# 24V_5V_Buck.net
KiCad netlist of a schematic drawn in Altium Designer
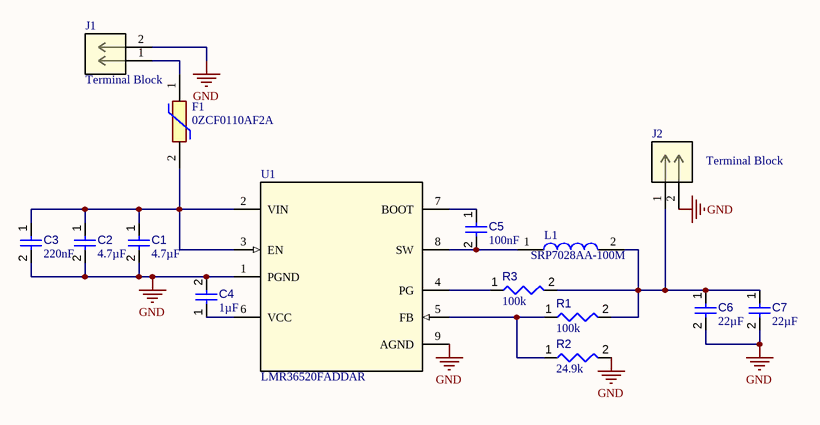
[diagram p0: 24V_5V_Buck.SchDoc]

(export (version "E")
  (design (tool "Eeschema 10.0.6"))
  (components
    (comp (ref "C1")
      (value "4.7µF")
      (footprint "CAPC0603(1608)100_L")
      (description "Chip Capacitor, 4.7µF +/-20%, 10V, 0603, Thickness 1 mm")
      (fields (field (name "TOLERANCE") "10%") (field (name "Comment") "Capacitor 4.7µF +/-20% 10V 0603"))
      (libsource (lib "Samuel Daniel Sdn67@UW") (part "CAP-NP-2"))
    )
    (comp (ref "C2")
      (value "4.7µF")
      (footprint "CAPC0603(1608)100_L")
      (description "Chip Capacitor, 4.7µF +/-20%, 10V, 0603, Thickness 1 mm")
      (fields (field (name "TOLERANCE") "10%") (field (name "Comment") "Capacitor 4.7µF +/-20% 10V 0603"))
      (libsource (lib "Samuel Daniel Sdn67@UW") (part "CAP-NP-2"))
    )
    (comp (ref "C3")
      (value "220nF")
      (footprint "CAPC0402(1005)60_L")
      (description "Chip Capacitor, 220nF +/-20%, 10V, 0402, Thickness 0.6 mm")
      (fields (field (name "TOLERANCE") "10%") (field (name "Comment") "Capacitor 220nF +/-20% 10V 0402"))
      (libsource (lib "Samuel Daniel Sdn67@UW") (part "CAP-NP-2"))
    )
    (comp (ref "C4")
      (value "1µF")
      (footprint "CAPC3216X180X20ML20")
      (description "Chip Capacitor, 1 uF, +/- 10%, 25 V, 1206 (3216 Metric)")
      (fields (field (name "TOLERANCE") "10%") (field (name "Comment") "Capacitor 1 uF +/- 10% 25 V 1206"))
      (libsource (lib "Samuel Daniel Sdn67@UW") (part "CAP-NP-2"))
    )
    (comp (ref "C5")
      (value "100nF")
      (footprint "CAPC2013X95X50LL10T25")
      (description "Chip Capacitor, 100 nF, +/- 10%, 50 V, 0805 (2012 Metric)")
      (fields (field (name "TOLERANCE") "10%") (field (name "Comment") "Capacitor 100 nF +/-10% 50 V 0805"))
      (libsource (lib "Samuel Daniel Sdn67@UW") (part "CAP-NP-2"))
    )
    (comp (ref "C6")
      (value "22µF")
      (footprint "CAPC0805(2012)145_L")
      (description "Chip Capacitor, 22µF +/-40%, 16V, 0805, Thickness 1.45 mm")
      (fields (field (name "TOLERANCE") "5%") (field (name "Comment") "Capacitor 22µF +/-40% 16V 0805"))
      (libsource (lib "Samuel Daniel Sdn67@UW") (part "CAP-NP-2"))
    )
    (comp (ref "C7")
      (value "22µF")
      (footprint "CAPC0805(2012)145_L")
      (description "Chip Capacitor, 22µF +/-40%, 16V, 0805, Thickness 1.45 mm")
      (fields (field (name "TOLERANCE") "5%") (field (name "Comment") "Capacitor 22µF +/-40% 16V 0805"))
      (libsource (lib "Samuel Daniel Sdn67@UW") (part "CAP-NP-2"))
    )
    (comp (ref "F1")
      (value "0ZCF0110AF2A")
      (footprint "SamacSys:FUSC7451X170N")
      (description "Resettable Fuse")
      (libsource (lib "SamacSys") (part "0ZCF0110AF2A"))
    )
    (comp (ref "J1")
      (value "Terminal Block")
      (footprint "CONN2_2710002_WRE")
      (description "WR-TBL Terminal block - Wire protector - THT")
      (fields
        (field (name "MANUFACTURER_PART_NUMBER") "691102710002")
        (field (name "COPYRIGHT") "Copyright (C) 2026 Ultra Librarian. All rights reserved.")
      )
      (libsource (lib "691102710002") (part "691102710002"))
    )
    (comp (ref "J2")
      (value "Terminal Block")
      (footprint "CONN2_2710002_WRE")
      (description "WR-TBL Terminal block - Wire protector - THT")
      (fields
        (field (name "MANUFACTURER_PART_NUMBER") "691102710002")
        (field (name "COPYRIGHT") "Copyright (C) 2026 Ultra Librarian. All rights reserved.")
      )
      (libsource (lib "") (part "691102710002_1"))
    )
    (comp (ref "L1")
      (value "SRP7028AA-100M")
      (footprint "INDPM7166X300N")
      (description "Inductor")
      (fields (field (name "MOUSER PART NUMBER") "652-SRP7028AA-100M"))
      (libsource (lib "*") (part "SRP7028AA-100M"))
    )
    (comp (ref "R1")
      (value "100k")
      (footprint "RESC0402(1005)_L")
      (description "Chip Resistor, 100 kOhms, +/-1 %, 63 mW, -55 to 155 degC, 0402")
      (fields (field (name "TOLERANCE") "1%") (field (name "POWER") "63mW"))
      (libsource (lib "Samuel Daniel Sdn67@UW") (part "RES-2"))
    )
    (comp (ref "R2")
      (value "24.9k")
      (footprint "RESC0402(1005)_L")
      (description "Chip Resistor, 24,9 kOhms, +/-1 %, 63 mW, -55 to 155 degC, 0402")
      (fields (field (name "TOLERANCE") "1%") (field (name "POWER") "63mW"))
      (libsource (lib "Samuel Daniel Sdn67@UW") (part "RES-2"))
    )
    (comp (ref "R3")
      (value "100k")
      (footprint "RESC0402(1005)_L")
      (description "Chip Resistor, 100 kOhms, +/-1 %, 63 mW, -55 to 155 degC, 0402")
      (fields (field (name "TOLERANCE") "1%") (field (name "POWER") "63mW"))
      (libsource (lib "Samuel Daniel Sdn67@UW") (part "RES-2"))
    )
    (comp (ref "U1")
      (value "LMR36520FADDAR")
      (footprint "DDA0008J")
      (fields (field (name "COPYRIGHT") "Copyright (C) 2025 Ultra Librarian. All rights reserved."))
      (libsource (lib "LMR36520FADDAR") (part "LMR36520FADDAR"))
    )
  )
  (nets
    (net (code "1") (name "GND") (class "Default")
      (node (ref "C1") (pin "2") (pinfunction "2_2") (pintype "passive"))
      (node (ref "C2") (pin "2") (pinfunction "2_2") (pintype "passive"))
      (node (ref "C3") (pin "2") (pinfunction "2_2") (pintype "passive"))
      (node (ref "C4") (pin "2") (pinfunction "2_2") (pintype "passive"))
      (node (ref "C6") (pin "2") (pinfunction "2_2") (pintype "passive"))
      (node (ref "C7") (pin "2") (pinfunction "2_2") (pintype "passive"))
      (node (ref "J1") (pin "2") (pinfunction "2_2") (pintype "passive"))
      (node (ref "J2") (pin "2") (pinfunction "2_2") (pintype "passive"))
      (node (ref "R2") (pin "2") (pinfunction "2_2") (pintype "passive"))
      (node (ref "U1") (pin "1") (pinfunction "PGND_1") (pintype "power_in"))
      (node (ref "U1") (pin "9") (pinfunction "AGND_9") (pintype "passive"))
    )
    (net (code "2") (name "Net-(C6-Pad1)") (class "Default")
      (node (ref "C6") (pin "1") (pinfunction "1_1") (pintype "passive"))
      (node (ref "C7") (pin "1") (pinfunction "1_1") (pintype "passive"))
      (node (ref "J2") (pin "1") (pinfunction "1_1") (pintype "passive"))
      (node (ref "L1") (pin "2") (pinfunction "2_2") (pintype "passive"))
      (node (ref "R1") (pin "2") (pinfunction "2_2") (pintype "passive"))
      (node (ref "R3") (pin "2") (pinfunction "2_2") (pintype "passive"))
    )
    (net (code "3") (name "Net-(F1-Pad1)") (class "Default")
      (node (ref "F1") (pin "1") (pinfunction "1_1") (pintype "passive"))
      (node (ref "J1") (pin "1") (pinfunction "1_1") (pintype "passive"))
    )
    (net (code "4") (name "Net-(U1-BOOT)") (class "Default")
      (node (ref "C5") (pin "1") (pinfunction "1_1") (pintype "passive"))
      (node (ref "U1") (pin "7") (pinfunction "BOOT_7") (pintype "power_in"))
    )
    (net (code "5") (name "Net-(U1-EN)") (class "Default")
      (node (ref "C1") (pin "1") (pinfunction "1_1") (pintype "passive"))
      (node (ref "C2") (pin "1") (pinfunction "1_1") (pintype "passive"))
      (node (ref "C3") (pin "1") (pinfunction "1_1") (pintype "passive"))
      (node (ref "F1") (pin "2") (pinfunction "2_2") (pintype "passive"))
      (node (ref "U1") (pin "2") (pinfunction "VIN_2") (pintype "power_in"))
      (node (ref "U1") (pin "3") (pinfunction "EN_3") (pintype "input"))
    )
    (net (code "6") (name "Net-(U1-FB)") (class "Default")
      (node (ref "R1") (pin "1") (pinfunction "1_1") (pintype "passive"))
      (node (ref "R2") (pin "1") (pinfunction "1_1") (pintype "passive"))
      (node (ref "U1") (pin "5") (pinfunction "FB_5") (pintype "input"))
    )
    (net (code "7") (name "Net-(U1-PG)") (class "Default")
      (node (ref "R3") (pin "1") (pinfunction "1_1") (pintype "passive"))
      (node (ref "U1") (pin "4") (pinfunction "PG_4") (pintype "open_collector"))
    )
    (net (code "8") (name "Net-(U1-SW)") (class "Default")
      (node (ref "C5") (pin "2") (pinfunction "2_2") (pintype "passive"))
      (node (ref "L1") (pin "1") (pinfunction "1_1") (pintype "passive"))
      (node (ref "U1") (pin "8") (pinfunction "SW_8") (pintype "power_in"))
    )
    (net (code "9") (name "Net-(U1-VCC)") (class "Default")
      (node (ref "C4") (pin "1") (pinfunction "1_1") (pintype "passive"))
      (node (ref "U1") (pin "6") (pinfunction "VCC_6") (pintype "power_in"))
    )
  )
)
